# POWER_STAGE.net
KiCad netlist of a schematic drawn in Altium Designer
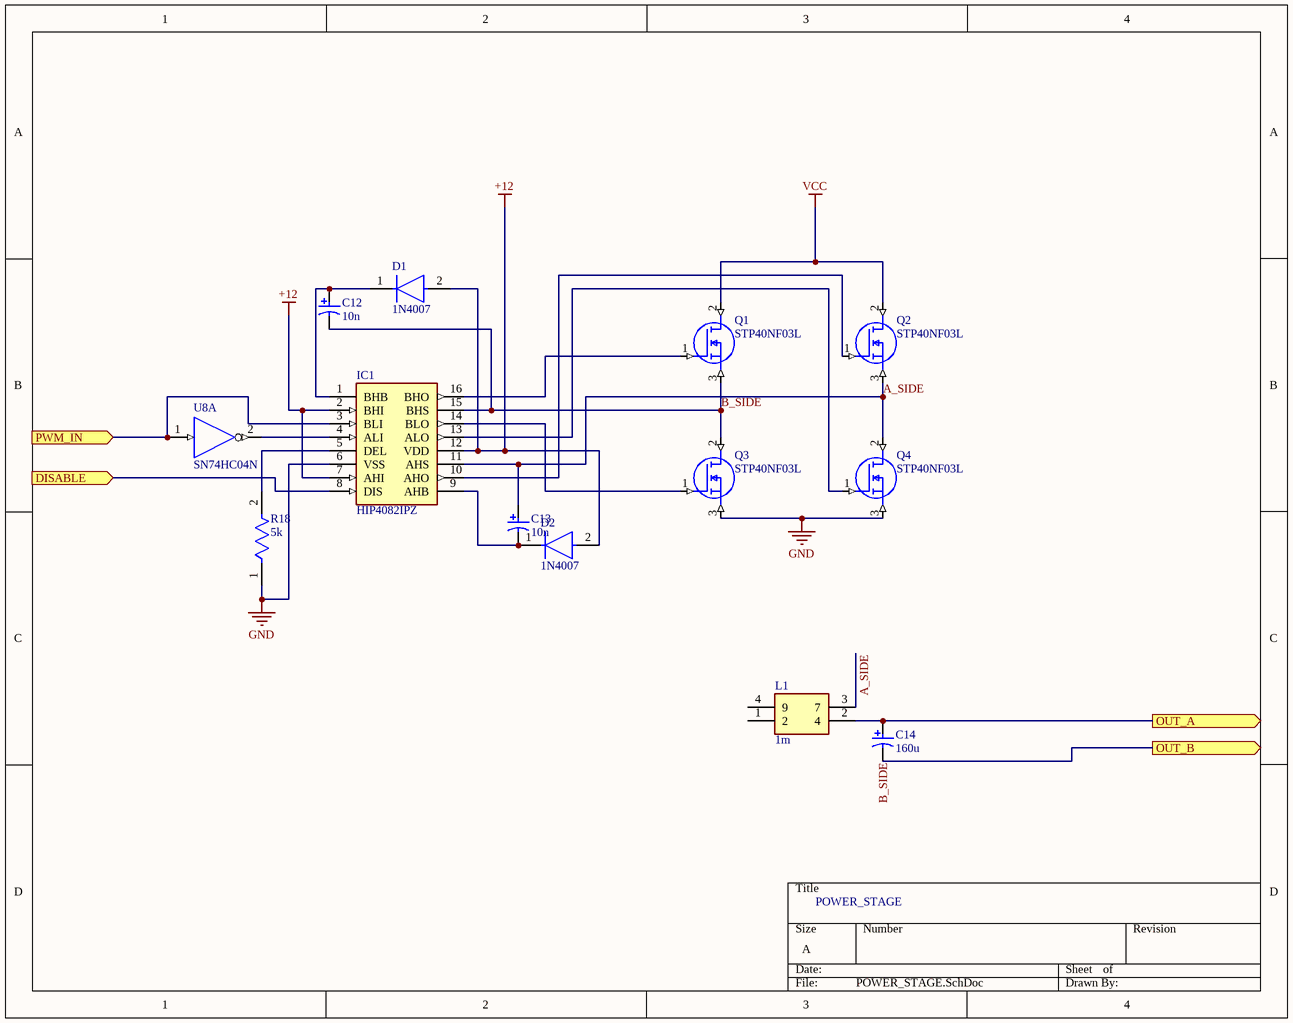
[diagram p0: POWER_STAGE.SchDoc]

(export (version "E")
  (design (tool "Eeschema 10.0.6"))
  (components
    (comp (ref "C12")
      (value "10n")
      (footprint "PNSC-ECA-1VM221-2")
      (description "Aluminum Electrolytic Capacitor, 220 uF, +/- 20%, 35 V, -40 to 85 degC, 2-Pin THD, RoHS, Bulk")
      (fields (field (name "MANUFACTURER") "Panasonic"))
      (libsource (lib "Altium Content Vault") (part "CAP-P-2"))
    )
    (comp (ref "C13")
      (value "10n")
      (footprint "PNSC-ECA-1VM221-2")
      (description "Aluminum Electrolytic Capacitor, 220 uF, +/- 20%, 35 V, -40 to 85 degC, 2-Pin THD, RoHS, Bulk")
      (fields (field (name "MANUFACTURER") "Panasonic"))
      (libsource (lib "Altium Content Vault") (part "CAP-P-2"))
    )
    (comp (ref "C14")
      (value "160u")
      (footprint "PNSC-ECA-1VM221-2")
      (description "Aluminum Electrolytic Capacitor, 220 uF, +/- 20%, 35 V, -40 to 85 degC, 2-Pin THD, RoHS, Bulk")
      (fields (field (name "MANUFACTURER") "Panasonic"))
      (libsource (lib "Altium Content Vault") (part "CAP-P-2"))
    )
    (comp (ref "D1")
      (value "1N4007")
      (footprint "FP-1N4007-MFG")
      (description "Rectifier diode 1000 V 1 A DO-41, ,")
      (fields
        (field (name "MANUFACTURER") "Diotec")
        (field (name "OCTOPART") "https://octopart.com/1n4007-diotec-4040411")
      )
      (libsource (lib "Altium Content Vault") (part "d7152d700b627762746794eb795d46e"))
    )
    (comp (ref "D2")
      (value "1N4007")
      (footprint "FP-1N4007-MFG")
      (description "Rectifier diode 1000 V 1 A DO-41, ,")
      (fields
        (field (name "MANUFACTURER") "Diotec")
        (field (name "OCTOPART") "https://octopart.com/1n4007-diotec-4040411")
      )
      (libsource (lib "Altium Content Vault") (part "d7152d700b627762746794eb795d46e"))
    )
    (comp (ref "IC1")
      (value "HIP4082IPZ")
      (footprint "SamacSys:DIP794W56P254L1917H533Q16N")
      (description "Integrated Circuit")
      (fields (field (name "MOUSER PART NUMBER") "968-HIP4082IPZ"))
      (libsource (lib "*") (part "HIP4082IPZ"))
    )
    (comp (ref "L1")
      (value "1m")
      (footprint "SamacSys:744824101")
      (description "Inductor")
      (fields
        (field (name "MANUFACTURER_PART_NUMBER") "744824101")
        (field (name "MOUSER PART NUMBER") "710-744824101")
      )
      (libsource (lib "*") (part "744824101"))
    )
    (comp (ref "Q1")
      (value "STP40NF03L")
      (footprint "SamacSys:TO254P470X1016X2019-3P")
      (description "MOSFET (N-Channel)")
      (fields
        (field (name "MANUFACTURER_PART_NUMBER") "FDP7030BL")
        (field (name "MOUSER PART NUMBER") "512-FDP7030BL")
      )
      (libsource (lib "*") (part "FDP7030BL"))
    )
    (comp (ref "Q2")
      (value "STP40NF03L")
      (footprint "SamacSys:TO254P470X1016X2019-3P")
      (description "MOSFET (N-Channel)")
      (fields
        (field (name "MANUFACTURER_PART_NUMBER") "FDP7030BL")
        (field (name "MOUSER PART NUMBER") "512-FDP7030BL")
      )
      (libsource (lib "*") (part "FDP7030BL"))
    )
    (comp (ref "Q3")
      (value "STP40NF03L")
      (footprint "SamacSys:TO254P470X1016X2019-3P")
      (description "MOSFET (N-Channel)")
      (fields
        (field (name "MANUFACTURER_PART_NUMBER") "FDP7030BL")
        (field (name "MOUSER PART NUMBER") "512-FDP7030BL")
      )
      (libsource (lib "*") (part "FDP7030BL"))
    )
    (comp (ref "Q4")
      (value "STP40NF03L")
      (footprint "SamacSys:TO254P470X1016X2019-3P")
      (description "MOSFET (N-Channel)")
      (fields
        (field (name "MANUFACTURER_PART_NUMBER") "FDP7030BL")
        (field (name "MOUSER PART NUMBER") "512-FDP7030BL")
      )
      (libsource (lib "*") (part "FDP7030BL"))
    )
    (comp (ref "R18")
      (value "5k")
      (footprint "FP-CF18-MFG")
      (description "RES 2.2K OHM 1/8W 5% CF AXIAL")
      (fields
        (field (name "OCTOPART") "https://octopart.com/cf18jt2k20-stackpole+electronics-19205714")
        (field (name "TOLERANCE") "5%")
      )
      (libsource (lib "Altium Content Vault") (part "1029c3af85768c4190bb7ad29bc67b5"))
    )
    (comp (ref "U8")
      (value "SN74HC04N")
      (footprint "N0014A")
      (description "Hex Inverters, N0014A, TUBE")
      (fields
        (field (name "MANUFACTURER") "Texas Instruments")
        (field (name "GENERIC PART NUMBER") "SN74HC04")
      )
      (libsource (lib "Altium Content Vault") (part "TI-CD_SNX4XXXXXX4X_19A-14"))
    )
  )
  (nets
    (net (code "1") (name "+12") (class "Default")
      (node (ref "D1") (pin "2") (pinfunction "A_2") (pintype "passive"))
      (node (ref "D2") (pin "2") (pinfunction "A_2") (pintype "passive"))
      (node (ref "IC1") (pin "12") (pinfunction "VDD_12") (pintype "power_in"))
      (node (ref "IC1") (pin "2") (pinfunction "BHI_2") (pintype "input"))
      (node (ref "IC1") (pin "7") (pinfunction "AHI_7") (pintype "input"))
    )
    (net (code "2") (name "/A_SIDE") (class "Default")
      (node (ref "C13") (pin "1") (pinfunction "1_1") (pintype "passive"))
      (node (ref "IC1") (pin "11") (pinfunction "AHS_11") (pintype "passive"))
      (node (ref "L1") (pin "3") (pinfunction "7_3") (pintype "passive"))
      (node (ref "Q2") (pin "3") (pinfunction "S_3") (pintype "input"))
      (node (ref "Q4") (pin "2") (pinfunction "D_2") (pintype "input"))
    )
    (net (code "3") (name "/B_SIDE") (class "Default")
      (node (ref "C12") (pin "2") (pinfunction "2_2") (pintype "passive"))
      (node (ref "C14") (pin "2") (pinfunction "2_2") (pintype "passive"))
      (node (ref "IC1") (pin "15") (pinfunction "BHS_15") (pintype "passive"))
      (node (ref "Q1") (pin "3") (pinfunction "S_3") (pintype "input"))
      (node (ref "Q3") (pin "2") (pinfunction "D_2") (pintype "input"))
    )
    (net (code "4") (name "/DISABLE") (class "Default")
      (node (ref "IC1") (pin "8") (pinfunction "DIS_8") (pintype "input"))
    )
    (net (code "5") (name "/OUT_A") (class "Default")
      (node (ref "C14") (pin "1") (pinfunction "1_1") (pintype "passive"))
      (node (ref "L1") (pin "2") (pinfunction "4_2") (pintype "passive"))
    )
    (net (code "6") (name "/PWM_IN") (class "Default")
      (node (ref "IC1") (pin "3") (pinfunction "BLI_3") (pintype "input"))
      (node (ref "U8") (pin "1") (pinfunction "1A_1") (pintype "input"))
    )
    (net (code "7") (name "GND") (class "Default")
      (node (ref "IC1") (pin "6") (pinfunction "VSS_6") (pintype "power_in"))
      (node (ref "Q3") (pin "3") (pinfunction "S_3") (pintype "input"))
      (node (ref "Q4") (pin "3") (pinfunction "S_3") (pintype "input"))
      (node (ref "R18") (pin "1") (pinfunction "1_1") (pintype "passive"))
    )
    (net (code "8") (name "Net-(D1-C)") (class "Default")
      (node (ref "C12") (pin "1") (pinfunction "1_1") (pintype "passive"))
      (node (ref "D1") (pin "1") (pinfunction "C_1") (pintype "passive"))
      (node (ref "IC1") (pin "1") (pinfunction "BHB_1") (pintype "passive"))
    )
    (net (code "9") (name "Net-(D2-C)") (class "Default")
      (node (ref "C13") (pin "2") (pinfunction "2_2") (pintype "passive"))
      (node (ref "D2") (pin "1") (pinfunction "C_1") (pintype "passive"))
      (node (ref "IC1") (pin "9") (pinfunction "AHB_9") (pintype "passive"))
    )
    (net (code "10") (name "Net-(IC1-AHO)") (class "Default")
      (node (ref "IC1") (pin "10") (pinfunction "AHO_10") (pintype "output"))
      (node (ref "Q2") (pin "1") (pinfunction "G_1") (pintype "input"))
    )
    (net (code "11") (name "Net-(IC1-ALI)") (class "Default")
      (node (ref "IC1") (pin "4") (pinfunction "ALI_4") (pintype "input"))
      (node (ref "U8") (pin "2") (pinfunction "~{1Y}_2") (pintype "output"))
    )
    (net (code "12") (name "Net-(IC1-ALO)") (class "Default")
      (node (ref "IC1") (pin "13") (pinfunction "ALO_13") (pintype "output"))
      (node (ref "Q4") (pin "1") (pinfunction "G_1") (pintype "input"))
    )
    (net (code "13") (name "Net-(IC1-BHO)") (class "Default")
      (node (ref "IC1") (pin "16") (pinfunction "BHO_16") (pintype "output"))
      (node (ref "Q1") (pin "1") (pinfunction "G_1") (pintype "input"))
    )
    (net (code "14") (name "Net-(IC1-BLO)") (class "Default")
      (node (ref "IC1") (pin "14") (pinfunction "BLO_14") (pintype "output"))
      (node (ref "Q3") (pin "1") (pinfunction "G_1") (pintype "input"))
    )
    (net (code "15") (name "Net-(IC1-DEL)") (class "Default")
      (node (ref "IC1") (pin "5") (pinfunction "DEL_5") (pintype "passive"))
      (node (ref "R18") (pin "2") (pinfunction "2_2") (pintype "passive"))
    )
    (net (code "16") (name "VCC") (class "Default")
      (node (ref "Q1") (pin "2") (pinfunction "D_2") (pintype "input"))
      (node (ref "Q2") (pin "2") (pinfunction "D_2") (pintype "input"))
    )
    (net (code "17") (name "unconnected-(L1-2-Pad1)") (class "Default")
      (node (ref "L1") (pin "1") (pinfunction "2_1") (pintype "passive"))
    )
    (net (code "18") (name "unconnected-(L1-9-Pad4)") (class "Default")
      (node (ref "L1") (pin "4") (pinfunction "9_4") (pintype "passive"))
    )
  )
)
